# CAN_DAC.net
KiCad netlist of a schematic drawn in Altium Designer
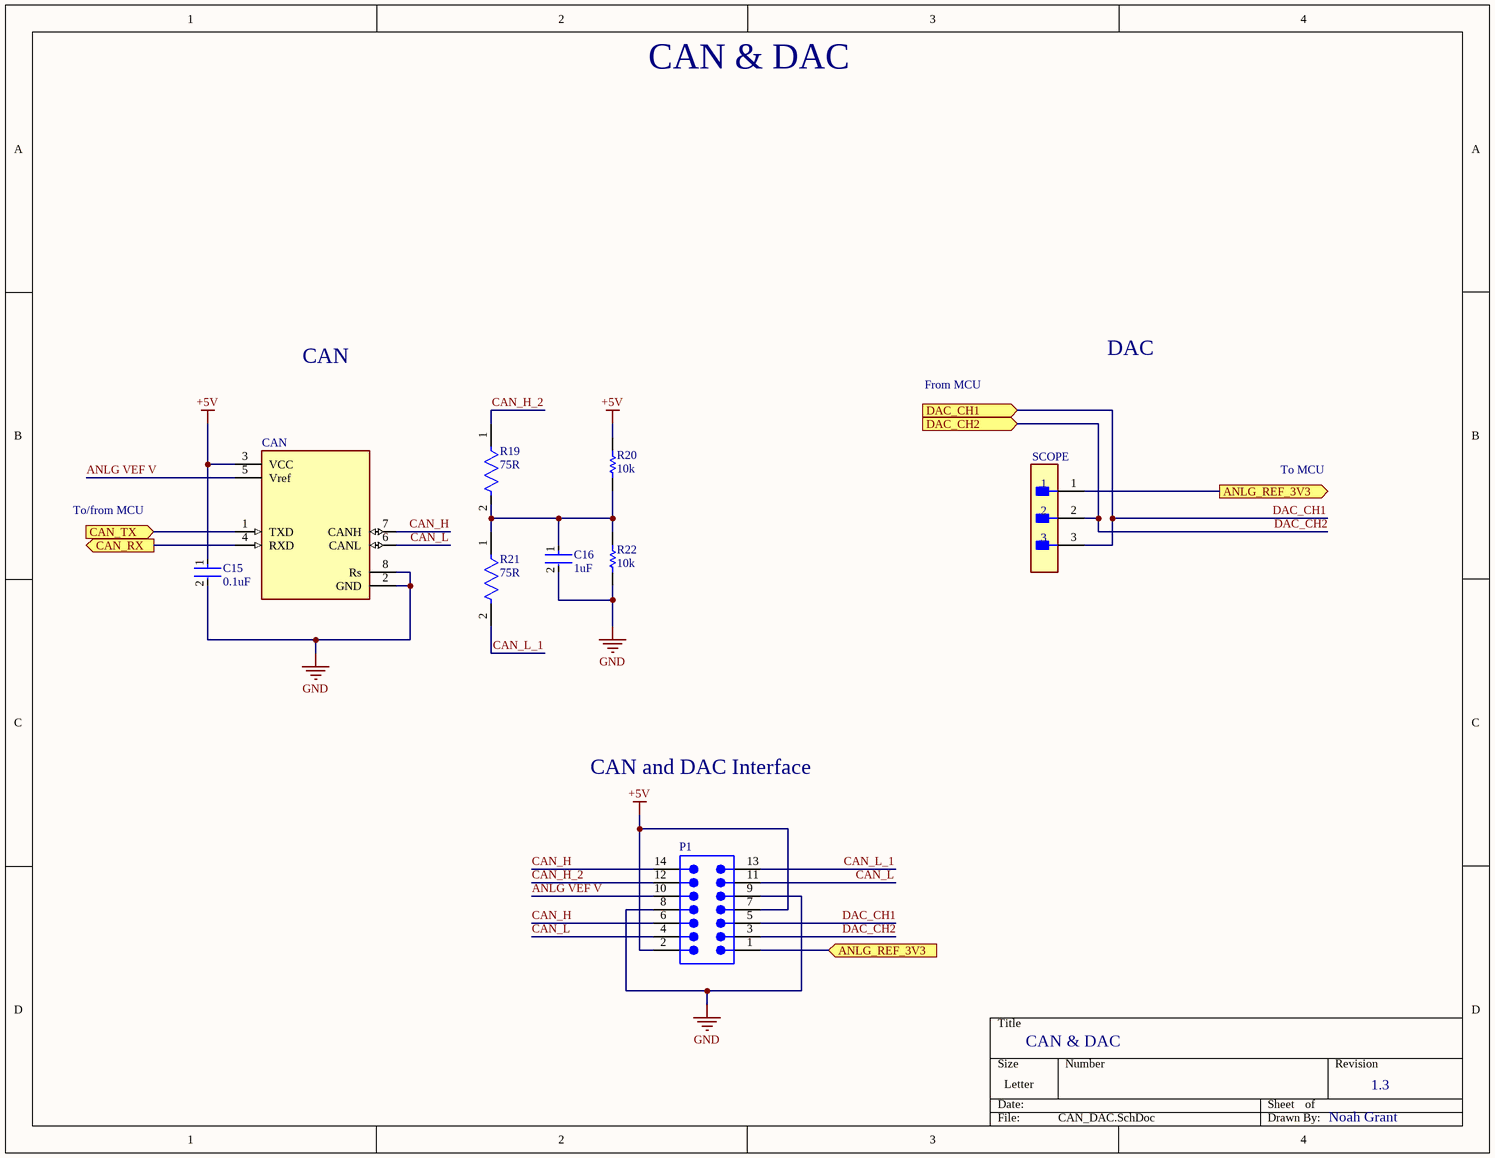
[diagram p0: CAN_DAC.SchDoc]

(export (version "E")
  (design (tool "Eeschema 10.0.6"))
  (components
    (comp (ref "C15")
      (value "0.1uF")
      (footprint "FP-CC0603-DA-MFG")
      (description "CAP CER 0.1UF 50V X7R 0603")
      (fields
        (field (name "MANUFACTURER") "YAGEO")
        (field (name "OCTOPART") "https://octopart.com/cc0603kpx7r9bb104-yageo-12885113")
      )
      (libsource (lib "Altium Content Vault") (part "11868f565c42a9108669ba33697ecf6"))
    )
    (comp (ref "C16")
      (value "1uF")
      (footprint "FP-C0603C105K3PACTU-MFG")
      (description "CAP CER 1UF 25V X5R 0603")
      (fields (field (name "VOLTAGE") "25V") (field (name "TOLERANCE") "10%"))
      (libsource (lib "Altium Content Vault") (part "e9c51b7dd13d4faca003ae77663ab08"))
    )
    (comp (ref "CAN")
      (value "PCA82C250T/YM,115")
      (footprint "FP-PCA82C250T-YM_115-MFG")
      (description "IC TRANSCEIVER HALF 1/1 8SO")
      (fields
        (field (name "OCTOPART") "https://octopart.com/pca82c250t%2Fym%2C115-nxp+semiconductors-18837169")
        (field (name "MANUFACTURER") "NXP Semiconductors")
      )
      (libsource (lib "Altium Content Vault") (part "27a24e0797d7391b7ad9f34746a8eee"))
    )
    (comp (ref "P1")
      (value "TSW-107-06-L-D")
      (footprint "SMTC-TSW-107-06-X-D")
      (description "0.025\" SQ Post Header, Through-hole, Vertical, -55 to 125 degC, 2.54 mm Pitch, 14-Pin, Male, RoHS")
      (fields (field (name "MANUFACTURER") "Samtec"))
      (libsource (lib "Altium Content Vault") (part "SMTC-TSW-107-X-X-D-X"))
    )
    (comp (ref "R19")
      (value "75R")
      (footprint "FP-RT0603-MFG")
      (description "RES SMD 75 OHM 1% 1/10W 0603")
      (fields (field (name "MANUFACTURER") "Yageo") (field (name "TOLERANCE") "0.01"))
      (libsource (lib "Altium Content Vault") (part "1029c3af85768c4190bb7ad29bc67b5"))
    )
    (comp (ref "R20")
      (value "10k")
      (footprint "RESC1609X50X30NL8T20")
      (description "Chip Resistor, 10 KOhm, +/- 1%, 100 mW, -55 to 155 degC, 0603 (1608 Metric), RoHS, Tape and Reel")
      (fields (field (name "MANUFACTURER") "Vishay Semiconductor"))
      (libsource (lib "Altium Content Vault") (part "RES-2"))
    )
    (comp (ref "R21")
      (value "75R")
      (footprint "FP-RT0603-MFG")
      (description "RES SMD 75 OHM 1% 1/10W 0603")
      (fields (field (name "MANUFACTURER") "Yageo") (field (name "TOLERANCE") "0.01"))
      (libsource (lib "Altium Content Vault") (part "1029c3af85768c4190bb7ad29bc67b5"))
    )
    (comp (ref "R22")
      (value "10k")
      (footprint "RESC1609X50X30NL8T20")
      (description "Chip Resistor, 10 KOhm, +/- 1%, 100 mW, -55 to 155 degC, 0603 (1608 Metric), RoHS, Tape and Reel")
      (fields (field (name "MANUFACTURER") "Vishay Semiconductor"))
      (libsource (lib "Altium Content Vault") (part "RES-2"))
    )
    (comp (ref "SCOPE")
      (value "22-29-2031")
      (footprint "FP-22-29-2031-MFG")
      (description "CONN HEADER VERT 3POS 2.54MM")
      (libsource (lib "Altium Content Vault") (part "0d3f023dd272f625e17a2be33dea85f"))
    )
  )
  (nets
    (net (code "1") (name "+5V") (class "Default")
      (node (ref "C15") (pin "1") (pinfunction "1_1") (pintype "passive"))
      (node (ref "CAN") (pin "3") (pinfunction "VCC_3") (pintype "power_in"))
      (node (ref "P1") (pin "2") (pinfunction "2_2") (pintype "passive"))
      (node (ref "P1") (pin "7") (pinfunction "7_7") (pintype "passive"))
      (node (ref "R20") (pin "2") (pinfunction "2_2") (pintype "passive"))
    )
    (net (code "2") (name "/ANLG VEF V") (class "Default")
      (node (ref "CAN") (pin "5") (pinfunction "Vref_5") (pintype "power_in"))
      (node (ref "P1") (pin "10") (pinfunction "10_10") (pintype "passive"))
    )
    (net (code "3") (name "/ANLG_REF_3V3") (class "Default")
      (node (ref "P1") (pin "1") (pinfunction "1_1") (pintype "passive"))
      (node (ref "SCOPE") (pin "1") (pinfunction "1_1") (pintype "passive"))
    )
    (net (code "4") (name "/CAN_H") (class "Default")
      (node (ref "CAN") (pin "7") (pinfunction "CANH_7") (pintype "bidirectional"))
      (node (ref "P1") (pin "14") (pinfunction "14_14") (pintype "passive"))
      (node (ref "P1") (pin "6") (pinfunction "6_6") (pintype "passive"))
    )
    (net (code "5") (name "/CAN_H_2") (class "Default")
      (node (ref "P1") (pin "12") (pinfunction "12_12") (pintype "passive"))
      (node (ref "R19") (pin "1") (pinfunction "1_1") (pintype "passive"))
    )
    (net (code "6") (name "/CAN_L") (class "Default")
      (node (ref "CAN") (pin "6") (pinfunction "CANL_6") (pintype "bidirectional"))
      (node (ref "P1") (pin "11") (pinfunction "11_11") (pintype "passive"))
      (node (ref "P1") (pin "4") (pinfunction "4_4") (pintype "passive"))
    )
    (net (code "7") (name "/CAN_L_1") (class "Default")
      (node (ref "P1") (pin "13") (pinfunction "13_13") (pintype "passive"))
      (node (ref "R21") (pin "2") (pinfunction "2_2") (pintype "passive"))
    )
    (net (code "8") (name "/CAN_RX") (class "Default")
      (node (ref "CAN") (pin "4") (pinfunction "RXD_4") (pintype "input"))
    )
    (net (code "9") (name "/CAN_TX") (class "Default")
      (node (ref "CAN") (pin "1") (pinfunction "TXD_1") (pintype "input"))
    )
    (net (code "10") (name "/DAC_CH1") (class "Default")
      (node (ref "P1") (pin "5") (pinfunction "5_5") (pintype "passive"))
      (node (ref "SCOPE") (pin "3") (pinfunction "3_3") (pintype "passive"))
    )
    (net (code "11") (name "/DAC_CH2") (class "Default")
      (node (ref "P1") (pin "3") (pinfunction "3_3") (pintype "passive"))
      (node (ref "SCOPE") (pin "2") (pinfunction "2_2") (pintype "passive"))
    )
    (net (code "12") (name "GND") (class "Default")
      (node (ref "C15") (pin "2") (pinfunction "2_2") (pintype "passive"))
      (node (ref "C16") (pin "2") (pinfunction "2_2") (pintype "passive"))
      (node (ref "CAN") (pin "2") (pinfunction "GND_2") (pintype "power_in"))
      (node (ref "CAN") (pin "8") (pinfunction "Rs_8") (pintype "passive"))
      (node (ref "P1") (pin "8") (pinfunction "8_8") (pintype "passive"))
      (node (ref "P1") (pin "9") (pinfunction "9_9") (pintype "passive"))
      (node (ref "R22") (pin "1") (pinfunction "1_1") (pintype "passive"))
    )
    (net (code "13") (name "Net-(C16-Pad1)") (class "Default")
      (node (ref "C16") (pin "1") (pinfunction "1_1") (pintype "passive"))
      (node (ref "R19") (pin "2") (pinfunction "2_2") (pintype "passive"))
      (node (ref "R20") (pin "1") (pinfunction "1_1") (pintype "passive"))
      (node (ref "R21") (pin "1") (pinfunction "1_1") (pintype "passive"))
      (node (ref "R22") (pin "2") (pinfunction "2_2") (pintype "passive"))
    )
  )
)
